# Grove_-_Collision_Sensor_V1_0.net
KiCad netlist of a schematic drawn in EAGLE
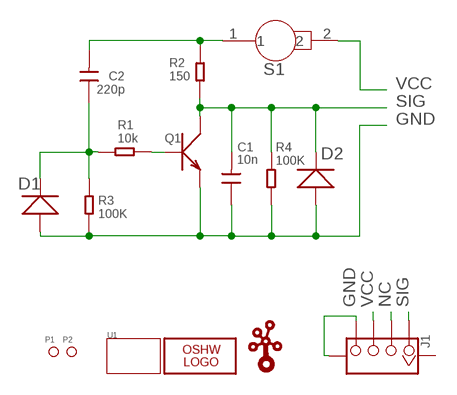
[diagram p0: schematic, sheet 1]

(export (version "E")
  (design (tool "Eeschema 10.0.6"))
  (components
    (comp (ref "C1")
      (value "10n")
      (footprint "eagle-import:0603")
      (libsource (lib "eagle-import") (part "C-0603"))
    )
    (comp (ref "C2")
      (value "220p")
      (footprint "eagle-import:0603")
      (libsource (lib "eagle-import") (part "C-0603"))
    )
    (comp (ref "D1")
      (value "D1N4148-SMD")
      (footprint "eagle-import:DO-35-SMD")
      (libsource (lib "eagle-import") (part "D1N4148-SMD"))
    )
    (comp (ref "D2")
      (value "D1N4148-SMD")
      (footprint "eagle-import:DO-35-SMD")
      (libsource (lib "eagle-import") (part "D1N4148-SMD"))
    )
    (comp (ref "J1")
      (value "TWIG-4P-2.0-SMD-FEMALE-REINFORCE'DD'")
      (footprint "eagle-import:4P-SMD-2.0")
      (libsource (lib "eagle-import") (part "TWIG-4P-2.0-SMD-FEMALE-REINFORCE'DD'"))
    )
    (comp (ref "LOGO1")
      (value "LOGO-OSHW-6MILX0200-NT")
      (footprint "eagle-import:OSHW_6X200_NOTEXT")
      (libsource (lib "eagle-import") (part "LOGO-OSHW-6MILX0200-NT"))
    )
    (comp (ref "P1")
      (value "PAD-MARK")
      (footprint "eagle-import:ROUND-MARK-0.635")
      (libsource (lib "eagle-import") (part "PAD-MARK"))
    )
    (comp (ref "P2")
      (value "PAD-MARK")
      (footprint "eagle-import:ROUND-MARK-0.635")
      (libsource (lib "eagle-import") (part "PAD-MARK"))
    )
    (comp (ref "Q1")
      (value "TRANSISTOR-NPN-SOT23''")
      (footprint "eagle-import:SOT23")
      (libsource (lib "eagle-import") (part "TRANSISTOR-NPN-SOT23''"))
    )
    (comp (ref "R1")
      (value "10k")
      (footprint "eagle-import:0603")
      (libsource (lib "eagle-import") (part "R-0603"))
    )
    (comp (ref "R2")
      (value "150")
      (footprint "eagle-import:0603")
      (libsource (lib "eagle-import") (part "R-0603"))
    )
    (comp (ref "R3")
      (value "100K")
      (footprint "eagle-import:0603")
      (libsource (lib "eagle-import") (part "R-0603"))
    )
    (comp (ref "R4")
      (value "100K")
      (footprint "eagle-import:0603")
      (libsource (lib "eagle-import") (part "R-0603"))
    )
    (comp (ref "S1")
      (value "SENSOR-COLLISION")
      (footprint "eagle-import:2P-ROUND-D5.4MM")
      (libsource (lib "eagle-import") (part "SENSOR-COLLISION"))
    )
    (comp (ref "U$2")
      (value "LOGO-TWIG")
      (footprint "eagle-import:TWIGLOGO")
      (libsource (lib "eagle-import") (part "LOGO-TWIG"))
    )
    (comp (ref "U1")
      (value "TWIG-1U")
      (footprint "eagle-import:1U-DIM-W_-DRILL")
      (libsource (lib "eagle-import") (part "TWIG-1U"))
    )
  )
  (nets
    (net (code "1") (name "/GND") (class "Default")
      (node (ref "C1") (pin "1") (pinfunction "1_1") (pintype "passive"))
      (node (ref "D1") (pin "A") (pinfunction "+_A") (pintype "passive"))
      (node (ref "D2") (pin "A") (pinfunction "+_A") (pintype "passive"))
      (node (ref "J1") (pin "4") (pinfunction "4_4") (pintype "bidirectional"))
      (node (ref "J1") (pin "SS2") (pinfunction "SS2_SS2") (pintype "bidirectional"))
      (node (ref "Q1") (pin "2") (pinfunction "E_2") (pintype "passive"))
      (node (ref "R3") (pin "2") (pinfunction "2_2") (pintype "passive"))
      (node (ref "R4") (pin "2") (pinfunction "2_2") (pintype "passive"))
    )
    (net (code "2") (name "/NC") (class "Default")
      (node (ref "J1") (pin "2") (pinfunction "2_2") (pintype "bidirectional"))
    )
    (net (code "3") (name "/SIG") (class "Default")
      (node (ref "C1") (pin "2") (pinfunction "2_2") (pintype "passive"))
      (node (ref "D2") (pin "C") (pinfunction "-_C") (pintype "passive"))
      (node (ref "J1") (pin "1") (pinfunction "1_1") (pintype "bidirectional"))
      (node (ref "Q1") (pin "3") (pinfunction "C_3") (pintype "passive"))
      (node (ref "R2") (pin "2") (pinfunction "2_2") (pintype "passive"))
      (node (ref "R4") (pin "1") (pinfunction "1_1") (pintype "passive"))
    )
    (net (code "4") (name "/VCC") (class "Default")
      (node (ref "J1") (pin "3") (pinfunction "3_3") (pintype "bidirectional"))
      (node (ref "S1") (pin "2") (pinfunction "2_2") (pintype "bidirectional"))
    )
    (net (code "5") (name "Net-(C2-Pad2)") (class "Default")
      (node (ref "C2") (pin "2") (pinfunction "2_2") (pintype "passive"))
      (node (ref "R2") (pin "1") (pinfunction "1_1") (pintype "passive"))
      (node (ref "S1") (pin "1") (pinfunction "1_1") (pintype "bidirectional"))
    )
    (net (code "6") (name "Net-(D1--)") (class "Default")
      (node (ref "C2") (pin "1") (pinfunction "1_1") (pintype "passive"))
      (node (ref "D1") (pin "C") (pinfunction "-_C") (pintype "passive"))
      (node (ref "R1") (pin "2") (pinfunction "2_2") (pintype "passive"))
      (node (ref "R3") (pin "1") (pinfunction "1_1") (pintype "passive"))
    )
    (net (code "7") (name "Net-(Q1-B)") (class "Default")
      (node (ref "Q1") (pin "1") (pinfunction "B_1") (pintype "passive"))
      (node (ref "R1") (pin "1") (pinfunction "1_1") (pintype "passive"))
    )
    (net (code "8") (name "unconnected-(J1-PadSS1)") (class "Default")
      (node (ref "J1") (pin "SS1") (pinfunction "SS1_SS1") (pintype "bidirectional"))
    )
  )
)
